# Bullseye_Volume_Board_Rev_0_0_2.net
KiCad netlist of a schematic drawn in Altium Designer
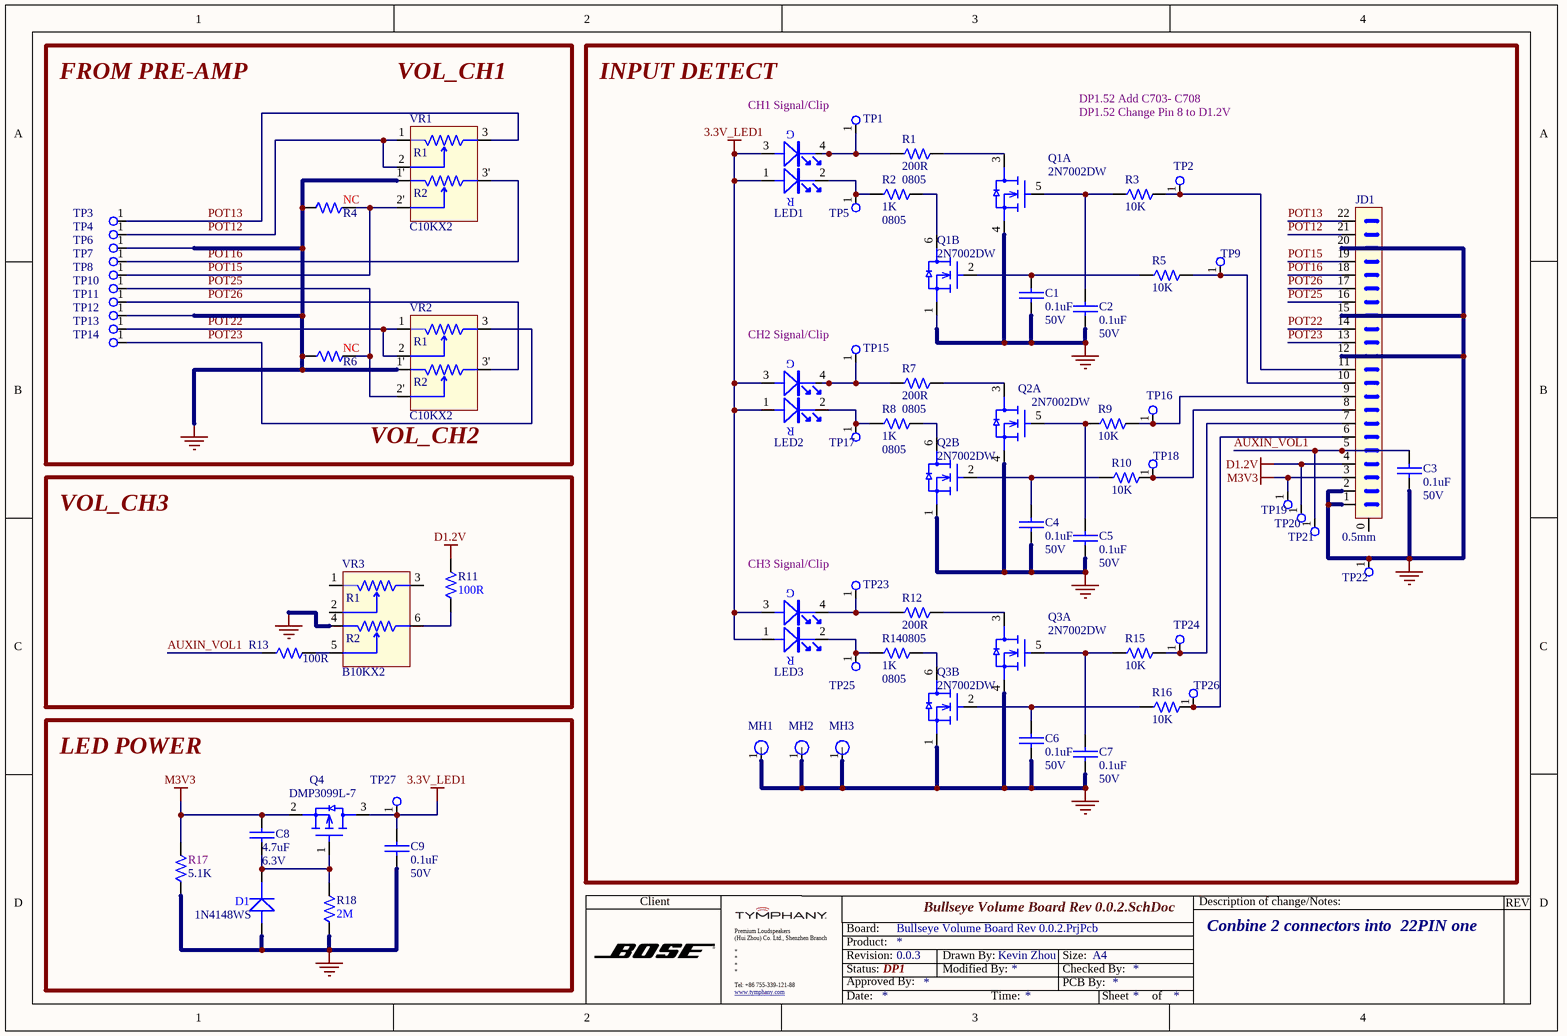
[diagram p0: Bullseye Volume Board Rev 0.0.2.SchDoc]

(export (version "E")
  (design (tool "Eeschema 10.0.6"))
  (components
    (comp (ref "C1")
      (value "0.1uF")
      (footprint "CAPC0402-RW")
      (description "CAP, CER, 0.1uF, 10%, 50V, X7R, 0402, RoHS")
      (fields
        (field (name "TOLERANCE") "10%")
        (field (name "VOLTAGE") "50V")
        (field (name "Comment") "PWL456470-1040")
        (field (name "CREATE_NAME") "TOM@Deftronics")
      )
      (libsource (lib "P-Capacitors") (part "CAP0402 0.1uF 50V 10%"))
    )
    (comp (ref "C2")
      (value "0.1uF")
      (footprint "CAPC0402-RW")
      (description "CAP, CER, 0.1uF, 10%, 50V, X7R, 0402, RoHS")
      (fields
        (field (name "TOLERANCE") "10%")
        (field (name "VOLTAGE") "50V")
        (field (name "Comment") "PWL456470-1040")
        (field (name "CREATE_NAME") "TOM@Deftronics")
      )
      (libsource (lib "P-Capacitors") (part "CAP0402 0.1uF 50V 10%"))
    )
    (comp (ref "C3")
      (value "0.1uF")
      (footprint "CAPC0402-RW")
      (description "CAP, CER, 0.1uF, 10%, 50V, X7R, 0402, RoHS")
      (fields
        (field (name "TOLERANCE") "10%")
        (field (name "VOLTAGE") "50V")
        (field (name "Comment") "PWL456470-1040")
        (field (name "CREATE_NAME") "TOM@Deftronics")
      )
      (libsource (lib "P-Capacitors") (part "CAP0402 0.1uF 50V 10%"))
    )
    (comp (ref "C4")
      (value "0.1uF")
      (footprint "CAPC0402-RW")
      (description "CAP, CER, 0.1uF, 10%, 50V, X7R, 0402, RoHS")
      (fields
        (field (name "TOLERANCE") "10%")
        (field (name "VOLTAGE") "50V")
        (field (name "Comment") "PWL456470-1040")
        (field (name "CREATE_NAME") "TOM@Deftronics")
      )
      (libsource (lib "P-Capacitors") (part "CAP0402 0.1uF 50V 10%"))
    )
    (comp (ref "C5")
      (value "0.1uF")
      (footprint "CAPC0402-RW")
      (description "CAP, CER, 0.1uF, 10%, 50V, X7R, 0402, RoHS")
      (fields
        (field (name "TOLERANCE") "10%")
        (field (name "VOLTAGE") "50V")
        (field (name "Comment") "PWL456470-1040")
        (field (name "CREATE_NAME") "TOM@Deftronics")
      )
      (libsource (lib "P-Capacitors") (part "CAP0402 0.1uF 50V 10%"))
    )
    (comp (ref "C6")
      (value "0.1uF")
      (footprint "CAPC0402-RW")
      (description "CAP, CER, 0.1uF, 10%, 50V, X7R, 0402, RoHS")
      (fields
        (field (name "TOLERANCE") "10%")
        (field (name "VOLTAGE") "50V")
        (field (name "Comment") "PWL456470-1040")
        (field (name "CREATE_NAME") "TOM@Deftronics")
      )
      (libsource (lib "P-Capacitors") (part "CAP0402 0.1uF 50V 10%"))
    )
    (comp (ref "C7")
      (value "0.1uF")
      (footprint "CAPC0402-RW")
      (description "CAP, CER, 0.1uF, 10%, 50V, X7R, 0402, RoHS")
      (fields
        (field (name "TOLERANCE") "10%")
        (field (name "VOLTAGE") "50V")
        (field (name "Comment") "PWL456470-1040")
        (field (name "CREATE_NAME") "TOM@Deftronics")
      )
      (libsource (lib "P-Capacitors") (part "CAP0402 0.1uF 50V 10%"))
    )
    (comp (ref "C8")
      (value "4.7uF")
      (footprint "CAPC0603-RW")
      (description "CHIP CAP 4.7uF 6.3V 10% 0603 TYPE X7R")
      (fields (field (name "MFG") "Walsin") (field (name "TOLERANCE") "10%") (field (name "VOLTAGE") "6.3V"))
      (libsource (lib "P-Capacitors") (part "CAP0603 4.7uF 6.3V 10% - Walsin"))
    )
    (comp (ref "C9")
      (value "0.1uF")
      (footprint "CAPC0603-RW")
      (description "GP CHIP CAP 0.1uF 50V 10% 0603 TYPE X7R")
      (fields
        (field (name "TOLERANCE") "10%")
        (field (name "VOLTAGE") "50V")
        (field (name "Comment") "PXL456470-1040")
      )
      (libsource (lib "P-Capacitors") (part "CAP0603 0.1uF 50V 10% - PXL456470-1040"))
    )
    (comp (ref "D1")
      (value "RCD114148-0020")
      (footprint "SOD-323")
      (description "DIODE SW 1N4148 VF=0.7V SOD-323")
      (fields
        (field (name "MFG") "TW SEMICONDUCTOR")
        (field (name "VOLTAGE") "100V")
        (field (name "MFG PART") "1N4148WS")
      )
      (libsource (lib "R-Semiconductors") (part "1N4148WS"))
    )
    (comp (ref "JD1")
      (value "0.5mm")
      (footprint "CONN FFC 22P PH=0.5mm SMT RA 0.5S-1X-22PWT-5.4R")
      (description "22P P=0.5MM 180 K")
      (fields
        (field (name "MFG") "金佳")
        (field (name "MFG PART") "0.5S-1X-22PWT-5.4R")
        (field (name "CREATE_NAME") "Nathan")
      )
      (libsource (lib "C-Connector") (part "CONN FFC 22P PH=0.5mm SMT RA 0.5S-1X-22PWT-5.4R"))
    )
    (comp (ref "LED1")
      (value "KCD250001-0010")
      (footprint "SMTLED2.0*1.25-RGB")
      (description "SMD LED 2.0x1.25mm MS-PTB2012CURSGAC  RED/GREEN")
      (fields
        (field (name "MFG PART") "MS-PTB2012CURSGAC  RED/GREEN")
        (field (name "MFG") "MASON")
        (field (name "CREATE_NAME") "TOM@Deftronics")
      )
      (libsource (lib "K-LED-FUSE") (part "MS-PTB2012CURSGAC"))
    )
    (comp (ref "LED2")
      (value "KCD250001-0010")
      (footprint "SMTLED2.0*1.25-RGB")
      (description "SMD LED 2.0x1.25mm MS-PTB2012CURSGAC  RED/GREEN")
      (fields
        (field (name "MFG PART") "MS-PTB2012CURSGAC  RED/GREEN")
        (field (name "MFG") "MASON")
        (field (name "CREATE_NAME") "TOM@Deftronics")
      )
      (libsource (lib "K-LED-FUSE") (part "MS-PTB2012CURSGAC"))
    )
    (comp (ref "LED3")
      (value "KCD250001-0010")
      (footprint "SMTLED2.0*1.25-RGB")
      (description "SMD LED 2.0x1.25mm MS-PTB2012CURSGAC  RED/GREEN")
      (fields
        (field (name "MFG PART") "MS-PTB2012CURSGAC  RED/GREEN")
        (field (name "MFG") "MASON")
        (field (name "CREATE_NAME") "TOM@Deftronics")
      )
      (libsource (lib "K-LED-FUSE") (part "MS-PTB2012CURSGAC"))
    )
    (comp (ref "MH1")
      (value "MHOLE 3MM")
      (footprint "MHOLE 3.5MM W/Vias")
      (description "MOUNTING HOLE FOR 3MM SCREW")
      (libsource (lib "Temporary") (part "MHOLE 3MM"))
    )
    (comp (ref "MH2")
      (value "MHOLE 3MM")
      (footprint "MHOLE 3.5MM W/Vias")
      (description "MOUNTING HOLE FOR 3MM SCREW")
      (libsource (lib "Temporary") (part "MHOLE 3MM"))
    )
    (comp (ref "MH3")
      (value "MHOLE 3MM")
      (footprint "MHOLE 3.5MM W/Vias")
      (description "MOUNTING HOLE FOR 3MM SCREW")
      (libsource (lib "Temporary") (part "MHOLE 3MM"))
    )
    (comp (ref "Q1")
      (value "RCM027002-1001")
      (footprint "SOT-363")
      (description "SMD MOSFET N-CH SOT-363 2N7002DW      Fairchild")
      (fields
        (field (name "MFG") "Fairchild")
        (field (name "MFG_PART") "2N7002DW")
        (field (name "CREATE_NAME") "Evan@Deftronics")
      )
      (libsource (lib "R-Semiconductors") (part "2N7002DW"))
    )
    (comp (ref "Q2")
      (value "RCM027002-1001")
      (footprint "SOT-363")
      (description "SMD MOSFET N-CH SOT-363 2N7002DW      Fairchild")
      (fields
        (field (name "MFG") "Fairchild")
        (field (name "MFG_PART") "2N7002DW")
        (field (name "CREATE_NAME") "Evan@Deftronics")
      )
      (libsource (lib "R-Semiconductors") (part "2N7002DW"))
    )
    (comp (ref "Q3")
      (value "RCM027002-1001")
      (footprint "SOT-363")
      (description "SMD MOSFET N-CH SOT-363 2N7002DW      Fairchild")
      (fields
        (field (name "MFG") "Fairchild")
        (field (name "MFG_PART") "2N7002DW")
        (field (name "CREATE_NAME") "Evan@Deftronics")
      )
      (libsource (lib "R-Semiconductors") (part "2N7002DW"))
    )
    (comp (ref "Q4")
      (value "T585002550438")
      (footprint "SOT23-132-RW")
      (description "PMOS 20V DMP3099L-7 SOT23 DIODES K")
      (fields
        (field (name "MFG") "DIODES  (ZETEX)")
        (field (name "MFG PART") "DMP3099L-7")
        (field (name "CREATE_NAME") "Nathan")
      )
      (libsource (lib "R-Semiconductors") (part "DMP3099L-7"))
    )
    (comp (ref "R1")
      (value "200R")
      (footprint "0805-RW")
      (description "GP CHIP RES. 200 OHM 1/8W 1% 0805")
      (fields (field (name "PACKAGE") "0805") (field (name "Comment") "QCF081020-2000"))
      (libsource (lib "Q-Resistors") (part "RES0805 1/8W 1% 200 OHM"))
    )
    (comp (ref "R2")
      (value "1K")
      (footprint "0805-RW")
      (description "GP CHIP RES. 1K OHM 1/8W 1% 0805")
      (fields (field (name "PACKAGE") "0805") (field (name "Comment") "QCF081020-1001"))
      (libsource (lib "Q-Resistors") (part "RES0805 1/8W 1% 1K OHM"))
    )
    (comp (ref "R3")
      (value "10K")
      (footprint "0402-RW")
      (description "CHIP RES 10K OHM 1/16W 1% 0402")
      (fields (field (name "MFG") "WALSIN") (field (name "Comment") "QCF161240-1002"))
      (libsource (lib "Q-Resistors") (part "RES0402 1/16W 1% 10K OHM"))
    )
    (comp (ref "R4")
      (value "NC")
      (footprint "0603-RW")
      (fields (field (name "Comment") "RES0603 NC") (field (name "CREATE_NAME") "Tom"))
      (libsource (lib "Temporary") (part "RES0603 NC"))
    )
    (comp (ref "R5")
      (value "10K")
      (footprint "0402-RW")
      (description "CHIP RES 10K OHM 1/16W 1% 0402")
      (fields (field (name "MFG") "WALSIN") (field (name "Comment") "QCF161240-1002"))
      (libsource (lib "Q-Resistors") (part "RES0402 1/16W 1% 10K OHM"))
    )
    (comp (ref "R6")
      (value "NC")
      (footprint "0603-RW")
      (fields (field (name "Comment") "RES0603 NC") (field (name "CREATE_NAME") "Tom"))
      (libsource (lib "Temporary") (part "RES0603 NC"))
    )
    (comp (ref "R7")
      (value "200R")
      (footprint "0805-RW")
      (description "GP CHIP RES. 200 OHM 1/8W 1% 0805")
      (fields (field (name "PACKAGE") "0805") (field (name "Comment") "QCF081020-2000"))
      (libsource (lib "Q-Resistors") (part "RES0805 1/8W 1% 200 OHM"))
    )
    (comp (ref "R8")
      (value "1K")
      (footprint "0805-RW")
      (description "GP CHIP RES. 1K OHM 1/8W 1% 0805")
      (fields (field (name "PACKAGE") "0805") (field (name "Comment") "QCF081020-1001"))
      (libsource (lib "Q-Resistors") (part "RES0805 1/8W 1% 1K OHM"))
    )
    (comp (ref "R9")
      (value "10K")
      (footprint "0402-RW")
      (description "CHIP RES 10K OHM 1/16W 1% 0402")
      (fields (field (name "MFG") "WALSIN") (field (name "Comment") "QCF161240-1002"))
      (libsource (lib "Q-Resistors") (part "RES0402 1/16W 1% 10K OHM"))
    )
    (comp (ref "R10")
      (value "10K")
      (footprint "0402-RW")
      (description "CHIP RES 10K OHM 1/16W 1% 0402")
      (fields (field (name "MFG") "WALSIN") (field (name "Comment") "QCF161240-1002"))
      (libsource (lib "Q-Resistors") (part "RES0402 1/16W 1% 10K OHM"))
    )
    (comp (ref "R11")
      (value "100R")
      (footprint "0402-RW")
      (description "CHIP RES 100 OHM 1/16W 1% 0402")
      (fields (field (name "MFG") "WALSIN") (field (name "Comment") "QCF161240-1000"))
      (libsource (lib "Q-Resistors") (part "RES0402 1/16W 1% 100 OHM"))
    )
    (comp (ref "R12")
      (value "200R")
      (footprint "0805-RW")
      (description "GP CHIP RES. 200 OHM 1/8W 1% 0805")
      (fields (field (name "PACKAGE") "0805") (field (name "Comment") "QCF081020-2000"))
      (libsource (lib "Q-Resistors") (part "RES0805 1/8W 1% 200 OHM"))
    )
    (comp (ref "R13")
      (value "100R")
      (footprint "0402-RW")
      (description "CHIP RES 100 OHM 1/16W 1% 0402")
      (fields (field (name "POWER") "1/16W") (field (name "MFG") "WALSIN"))
      (libsource (lib "Q-Resistors") (part "RES0402 1/16W 1% 100 OHM"))
    )
    (comp (ref "R14")
      (value "1K")
      (footprint "0805-RW")
      (description "GP CHIP RES. 1K OHM 1/8W 1% 0805")
      (fields (field (name "PACKAGE") "0805") (field (name "Comment") "QCF081020-1001"))
      (libsource (lib "Q-Resistors") (part "RES0805 1/8W 1% 1K OHM"))
    )
    (comp (ref "R15")
      (value "10K")
      (footprint "0402-RW")
      (description "CHIP RES 10K OHM 1/16W 1% 0402")
      (fields (field (name "MFG") "WALSIN") (field (name "Comment") "QCF161240-1002"))
      (libsource (lib "Q-Resistors") (part "RES0402 1/16W 1% 10K OHM"))
    )
    (comp (ref "R16")
      (value "10K")
      (footprint "0402-RW")
      (description "CHIP RES 10K OHM 1/16W 1% 0402")
      (fields (field (name "MFG") "WALSIN") (field (name "Comment") "QCF161240-1002"))
      (libsource (lib "Q-Resistors") (part "RES0402 1/16W 1% 10K OHM"))
    )
    (comp (ref "R17")
      (value "5.1K")
      (footprint "0603-RW")
      (description "GP CHIP RES. 5.1K OHM 1/10W 1% 0603")
      (fields (field (name "Comment") "QCF011030-5101"))
      (libsource (lib "Q-Resistors") (part "RES0603 1/10W 1% 5.1K OHM"))
    )
    (comp (ref "R18")
      (value "2M")
      (footprint "0402-RW")
      (description "CHIP 2M OHM    100PPM +-1% 0402 WALS L")
      (fields
        (field (name "MFG") "WALSIN (華新)")
        (field (name "POWER") "1/16W")
        (field (name "CREATE_NAME") "Nathan")
      )
      (libsource (lib "Q-Resistors") (part "RES0402 1/16W 1% 2M OMH_WALSIN"))
    )
    (comp (ref "TP1")
      (value "CH1_GN")
      (footprint "TP_1.2mm")
      (description "TP")
      (libsource (lib "Temporary") (part "TP"))
    )
    (comp (ref "TP2")
      (value "CH1_SIG")
      (footprint "TP_1.2mm")
      (description "TP")
      (libsource (lib "Temporary") (part "TP"))
    )
    (comp (ref "TP3")
      (value "CH1_GN")
      (footprint "TP_1.2mm")
      (description "TP")
      (libsource (lib "Temporary") (part "TP"))
    )
    (comp (ref "TP4")
      (value "CH1_GN")
      (footprint "TP_1.2mm")
      (description "TP")
      (libsource (lib "Temporary") (part "TP"))
    )
    (comp (ref "TP5")
      (value "CH1_RED")
      (footprint "TP_1.2mm")
      (description "TP")
      (libsource (lib "Temporary") (part "TP"))
    )
    (comp (ref "TP6")
      (value "CH1_GN")
      (footprint "TP_1.2mm")
      (description "TP")
      (libsource (lib "Temporary") (part "TP"))
    )
    (comp (ref "TP7")
      (value "CH1_GN")
      (footprint "TP_1.2mm")
      (description "TP")
      (libsource (lib "Temporary") (part "TP"))
    )
    (comp (ref "TP8")
      (value "CH1_GN")
      (footprint "TP_1.2mm")
      (description "TP")
      (libsource (lib "Temporary") (part "TP"))
    )
    (comp (ref "TP9")
      (value "CH1_LIM")
      (footprint "TP_1.2mm")
      (description "TP")
      (libsource (lib "Temporary") (part "TP"))
    )
    (comp (ref "TP10")
      (value "CH1_GN")
      (footprint "TP_1.2mm")
      (description "TP")
      (libsource (lib "Temporary") (part "TP"))
    )
    (comp (ref "TP11")
      (value "CH1_GN")
      (footprint "TP_1.2mm")
      (description "TP")
      (libsource (lib "Temporary") (part "TP"))
    )
    (comp (ref "TP12")
      (value "CH1_GN")
      (footprint "TP_1.2mm")
      (description "TP")
      (libsource (lib "Temporary") (part "TP"))
    )
    (comp (ref "TP13")
      (value "CH1_GN")
      (footprint "TP_1.2mm")
      (description "TP")
      (libsource (lib "Temporary") (part "TP"))
    )
    (comp (ref "TP14")
      (value "CH1_GN")
      (footprint "TP_1.2mm")
      (description "TP")
      (libsource (lib "Temporary") (part "TP"))
    )
    (comp (ref "TP15")
      (value "CH1_GN")
      (footprint "TP_1.2mm")
      (description "TP")
      (libsource (lib "Temporary") (part "TP"))
    )
    (comp (ref "TP16")
      (value "CH1_SIG")
      (footprint "TP_1.2mm")
      (description "TP")
      (libsource (lib "Temporary") (part "TP"))
    )
    (comp (ref "TP17")
      (value "CH1_RED")
      (footprint "TP_1.2mm")
      (description "TP")
      (libsource (lib "Temporary") (part "TP"))
    )
    (comp (ref "TP18")
      (value "CH1_LIM")
      (footprint "TP_1.2mm")
      (description "TP")
      (libsource (lib "Temporary") (part "TP"))
    )
    (comp (ref "TP19")
      (value "CH1_LIM")
      (footprint "TP_1.2mm")
      (description "TP")
      (libsource (lib "Temporary") (part "TP"))
    )
    (comp (ref "TP20")
      (value "CH1_LIM")
      (footprint "TP_1.2mm")
      (description "TP")
      (libsource (lib "Temporary") (part "TP"))
    )
    (comp (ref "TP21")
      (value "CH1_LIM")
      (footprint "TP_1.2mm")
      (description "TP")
      (libsource (lib "Temporary") (part "TP"))
    )
    (comp (ref "TP22")
      (value "CH1_LIM")
      (footprint "TP_1.2mm")
      (description "TP")
      (libsource (lib "Temporary") (part "TP"))
    )
    (comp (ref "TP23")
      (value "CH1_GN")
      (footprint "TP_1.2mm")
      (description "TP")
      (libsource (lib "Temporary") (part "TP"))
    )
    (comp (ref "TP24")
      (value "CH1_SIG")
      (footprint "TP_1.2mm")
      (description "TP")
      (libsource (lib "Temporary") (part "TP"))
    )
    (comp (ref "TP25")
      (value "CH1_RED")
      (footprint "TP_1.2mm")
      (description "TP")
      (libsource (lib "Temporary") (part "TP"))
    )
    (comp (ref "TP26")
      (value "CH1_LIM")
      (footprint "TP_1.2mm")
      (description "TP")
      (libsource (lib "Temporary") (part "TP"))
    )
    (comp (ref "TP27")
      (value "CH2_SIG")
      (footprint "TP_1.2mm")
      (description "TP")
      (libsource (lib "Temporary") (part "TP"))
    )
    (comp (ref "VR1")
      (value "C10KX2")
      (footprint "R11122G-FA20B7-5C103-167")
      (description "VR CA 10K C L=20MM R11122G-F K")
      (fields
        (field (name "MFG") "IDEAL")
        (field (name "MFG PART") "R11122G-FA20B7-5C103-167")
        (field (name "CREATE_NAME") "Nathan")
      )
      (libsource (lib "M-Controls") (part "R11122G-FA20B7-5C103-167"))
    )
    (comp (ref "VR2")
      (value "C10KX2")
      (footprint "R11122G-FA20B7-5C103-167")
      (description "VR CA 10K C L=20MM R11122G-F K")
      (fields
        (field (name "MFG") "IDEAL")
        (field (name "MFG PART") "R11122G-FA20B7-5C103-167")
        (field (name "CREATE_NAME") "Nathan")
      )
      (libsource (lib "M-Controls") (part "R11122G-FA20B7-5C103-167"))
    )
    (comp (ref "VR3")
      (value "B10KX2")
      (footprint "RV112BCF-40-20A-B10K-0C")
      (description "VR CA 10K B 15.4X13MM RV112BCF- K")
      (fields
        (field (name "MFG") "ALPHA    (東莞艾華電子)")
        (field (name "MFG PART") "RV112BCF-40-20A-B10K-0C")
        (field (name "CREATE_NAME") "Nathan")
      )
      (libsource (lib "M-Controls") (part "RV112BCF-40-20A-B10K-0C"))
    )
  )
  (nets
    (net (code "1") (name "/AUXIN_VOL1") (class "Default")
      (node (ref "C3") (pin "1") (pinfunction "1_1") (pintype "passive"))
      (node (ref "JD1") (pin "5") (pinfunction "5_5") (pintype "passive"))
      (node (ref "R13") (pin "1") (pinfunction "1_1") (pintype "passive"))
      (node (ref "TP21") (pin "1") (pinfunction "1_1") (pintype "passive"))
    )
    (net (code "2") (name "/POT12") (class "Default")
      (node (ref "JD1") (pin "21") (pinfunction "21_21") (pintype "passive"))
      (node (ref "TP4") (pin "1") (pinfunction "1_1") (pintype "passive"))
      (node (ref "VR1") (pin "1") (pinfunction "1_1") (pintype "passive"))
      (node (ref "VR1") (pin "2") (pinfunction "2_2") (pintype "passive"))
    )
    (net (code "3") (name "/POT13") (class "Default")
      (node (ref "JD1") (pin "22") (pinfunction "22_22") (pintype "passive"))
      (node (ref "TP3") (pin "1") (pinfunction "1_1") (pintype "passive"))
      (node (ref "VR1") (pin "3") (pinfunction "3_3") (pintype "passive"))
    )
    (net (code "4") (name "/POT15") (class "Default")
      (node (ref "JD1") (pin "19") (pinfunction "19_19") (pintype "passive"))
      (node (ref "R4") (pin "1") (pinfunction "1_1") (pintype "passive"))
      (node (ref "TP8") (pin "1") (pinfunction "1_1") (pintype "passive"))
      (node (ref "VR1") (pin "2'") (pinfunction "2'_2'") (pintype "passive"))
    )
    (net (code "5") (name "/POT16") (class "Default")
      (node (ref "JD1") (pin "18") (pinfunction "18_18") (pintype "passive"))
      (node (ref "TP7") (pin "1") (pinfunction "1_1") (pintype "passive"))
      (node (ref "VR1") (pin "3'") (pinfunction "3'_3'") (pintype "passive"))
    )
    (net (code "6") (name "/POT22") (class "Default")
      (node (ref "JD1") (pin "14") (pinfunction "14_14") (pintype "passive"))
      (node (ref "TP13") (pin "1") (pinfunction "1_1") (pintype "passive"))
      (node (ref "VR2") (pin "1") (pinfunction "1_1") (pintype "passive"))
      (node (ref "VR2") (pin "2") (pinfunction "2_2") (pintype "passive"))
    )
    (net (code "7") (name "/POT23") (class "Default")
      (node (ref "JD1") (pin "13") (pinfunction "13_13") (pintype "passive"))
      (node (ref "TP14") (pin "1") (pinfunction "1_1") (pintype "passive"))
      (node (ref "VR2") (pin "3") (pinfunction "3_3") (pintype "passive"))
    )
    (net (code "8") (name "/POT25") (class "Default")
      (node (ref "JD1") (pin "16") (pinfunction "16_16") (pintype "passive"))
      (node (ref "R6") (pin "2") (pinfunction "2_2") (pintype "passive"))
      (node (ref "TP10") (pin "1") (pinfunction "1_1") (pintype "passive"))
      (node (ref "VR2") (pin "2'") (pinfunction "2'_2'") (pintype "passive"))
    )
    (net (code "9") (name "/POT26") (class "Default")
      (node (ref "JD1") (pin "17") (pinfunction "17_17") (pintype "passive"))
      (node (ref "TP11") (pin "1") (pinfunction "1_1") (pintype "passive"))
      (node (ref "VR2") (pin "3'") (pinfunction "3'_3'") (pintype "passive"))
    )
    (net (code "10") (name "3.3V_LED1") (class "Default")
      (node (ref "C9") (pin "2") (pinfunction "2_2") (pintype "passive"))
      (node (ref "LED1") (pin "1") (pinfunction "1_1") (pintype "passive"))
      (node (ref "LED1") (pin "3") (pinfunction "3_3") (pintype "passive"))
      (node (ref "LED2") (pin "1") (pinfunction "1_1") (pintype "passive"))
      (node (ref "LED2") (pin "3") (pinfunction "3_3") (pintype "passive"))
      (node (ref "LED3") (pin "1") (pinfunction "1_1") (pintype "passive"))
      (node (ref "LED3") (pin "3") (pinfunction "3_3") (pintype "passive"))
      (node (ref "Q4") (pin "3") (pinfunction "D_3") (pintype "passive"))
      (node (ref "TP27") (pin "1") (pinfunction "1_1") (pintype "passive"))
    )
    (net (code "11") (name "D1.2V") (class "Default")
      (node (ref "JD1") (pin "4") (pinfunction "4_4") (pintype "passive"))
      (node (ref "R11") (pin "2") (pinfunction "2_2") (pintype "passive"))
      (node (ref "TP20") (pin "1") (pinfunction "1_1") (pintype "passive"))
    )
    (net (code "12") (name "GND") (class "Default")
      (node (ref "C1") (pin "2") (pinfunction "2_2") (pintype "passive"))
      (node (ref "C2") (pin "2") (pinfunction "2_2") (pintype "passive"))
      (node (ref "C3") (pin "2") (pinfunction "2_2") (pintype "passive"))
      (node (ref "C4") (pin "2") (pinfunction "2_2") (pintype "passive"))
      (node (ref "C5") (pin "2") (pinfunction "2_2") (pintype "passive"))
      (node (ref "C6") (pin "2") (pinfunction "2_2") (pintype "passive"))
      (node (ref "C7") (pin "2") (pinfunction "2_2") (pintype "passive"))
      (node (ref "C9") (pin "1") (pinfunction "1_1") (pintype "passive"))
      (node (ref "D1") (pin "1") (pinfunction "A_1") (pintype "passive"))
      (node (ref "JD1") (pin "1") (pinfunction "1_1") (pintype "passive"))
      (node (ref "JD1") (pin "12") (pinfunction "12_12") (pintype "passive"))
      (node (ref "JD1") (pin "15") (pinfunction "15_15") (pintype "passive"))
      (node (ref "JD1") (pin "2") (pinfunction "2_2") (pintype "passive"))
      (node (ref "JD1") (pin "20") (pinfunction "20_20") (pintype "passive"))
      (node (ref "MH1") (pin "1") (pinfunction "1_1") (pintype "passive"))
      (node (ref "MH2") (pin "1") (pinfunction "1_1") (pintype "passive"))
      (node (ref "MH3") (pin "1") (pinfunction "1_1") (pintype "passive"))
      (node (ref "Q1") (pin "1") (pinfunction "S_1") (pintype "passive"))
      (node (ref "Q1") (pin "4") (pinfunction "S_4") (pintype "passive"))
      (node (ref "Q2") (pin "1") (pinfunction "S_1") (pintype "passive"))
      (node (ref "Q2") (pin "4") (pinfunction "S_4") (pintype "passive"))
      (node (ref "Q3") (pin "1") (pinfunction "S_1") (pintype "passive"))
      (node (ref "Q3") (pin "4") (pinfunction "S_4") (pintype "passive"))
      (node (ref "R17") (pin "1") (pinfunction "1_1") (pintype "passive"))
      (node (ref "R18") (pin "1") (pinfunction "1_1") (pintype "passive"))
      (node (ref "R4") (pin "2") (pinfunction "2_2") (pintype "passive"))
      (node (ref "R6") (pin "1") (pinfunction "1_1") (pintype "passive"))
      (node (ref "TP12") (pin "1") (pinfunction "1_1") (pintype "passive"))
      (node (ref "TP22") (pin "1") (pinfunction "1_1") (pintype "passive"))
      (node (ref "TP6") (pin "1") (pinfunction "1_1") (pintype "passive"))
      (node (ref "VR1") (pin "1'") (pinfunction "1'_1'") (pintype "passive"))
      (node (ref "VR2") (pin "1'") (pinfunction "1'_1'") (pintype "passive"))
      (node (ref "VR3") (pin "4") (pinfunction "4_4") (pintype "passive"))
    )
    (net (code "13") (name "M3V3") (class "Default")
      (node (ref "C8") (pin "1") (pinfunction "1_1") (pintype "passive"))
      (node (ref "JD1") (pin "3") (pinfunction "3_3") (pintype "passive"))
      (node (ref "Q4") (pin "2") (pinfunction "S_2") (pintype "passive"))
      (node (ref "R17") (pin "2") (pinfunction "2_2") (pintype "passive"))
      (node (ref "TP19") (pin "1") (pinfunction "1_1") (pintype "passive"))
    )
    (net (code "14") (name "Net-(D1-K)") (class "Default")
      (node (ref "C8") (pin "2") (pinfunction "2_2") (pintype "passive"))
      (node (ref "D1") (pin "2") (pinfunction "K_2") (pintype "passive"))
      (node (ref "Q4") (pin "1") (pinfunction "G_1") (pintype "passive"))
      (node (ref "R18") (pin "2") (pinfunction "2_2") (pintype "passive"))
    )
    (net (code "15") (name "Net-(JD1-Pad6)") (class "Default")
      (node (ref "JD1") (pin "6") (pinfunction "6_6") (pintype "passive"))
      (node (ref "R16") (pin "2") (pinfunction "2_2") (pintype "passive"))
      (node (ref "TP26") (pin "1") (pinfunction "1_1") (pintype "passive"))
    )
    (net (code "16") (name "Net-(JD1-Pad7)") (class "Default")
      (node (ref "JD1") (pin "7") (pinfunction "7_7") (pintype "passive"))
      (node (ref "R15") (pin "2") (pinfunction "2_2") (pintype "passive"))
      (node (ref "TP24") (pin "1") (pinfunction "1_1") (pintype "passive"))
    )
    (net (code "17") (name "Net-(JD1-Pad8)") (class "Default")
      (node (ref "JD1") (pin "8") (pinfunction "8_8") (pintype "passive"))
      (node (ref "R10") (pin "2") (pinfunction "2_2") (pintype "passive"))
      (node (ref "TP18") (pin "1") (pinfunction "1_1") (pintype "passive"))
    )
    (net (code "18") (name "Net-(JD1-Pad9)") (class "Default")
      (node (ref "JD1") (pin "9") (pinfunction "9_9") (pintype "passive"))
      (node (ref "R9") (pin "2") (pinfunction "2_2") (pintype "passive"))
      (node (ref "TP16") (pin "1") (pinfunction "1_1") (pintype "passive"))
    )
    (net (code "19") (name "Net-(JD1-Pad10)") (class "Default")
      (node (ref "JD1") (pin "10") (pinfunction "10_10") (pintype "passive"))
      (node (ref "R5") (pin "2") (pinfunction "2_2") (pintype "passive"))
      (node (ref "TP9") (pin "1") (pinfunction "1_1") (pintype "passive"))
    )
    (net (code "20") (name "Net-(JD1-Pad11)") (class "Default")
      (node (ref "JD1") (pin "11") (pinfunction "11_11") (pintype "passive"))
      (node (ref "R3") (pin "2") (pinfunction "2_2") (pintype "passive"))
      (node (ref "TP2") (pin "1") (pinfunction "1_1") (pintype "passive"))
    )
    (net (code "21") (name "Net-(LED1-Pad2)") (class "Default")
      (node (ref "LED1") (pin "2") (pinfunction "2_2") (pintype "passive"))
      (node (ref "R2") (pin "1") (pinfunction "1_1") (pintype "passive"))
      (node (ref "TP5") (pin "1") (pinfunction "1_1") (pintype "passive"))
    )
    (net (code "22") (name "Net-(LED1-Pad4)") (class "Default")
      (node (ref "LED1") (pin "4") (pinfunction "4_4") (pintype "passive"))
      (node (ref "R1") (pin "1") (pinfunction "1_1") (pintype "passive"))
      (node (ref "TP1") (pin "1") (pinfunction "1_1") (pintype "passive"))
    )
    (net (code "23") (name "Net-(LED2-Pad2)") (class "Default")
      (node (ref "LED2") (pin "2") (pinfunction "2_2") (pintype "passive"))
      (node (ref "R8") (pin "1") (pinfunction "1_1") (pintype "passive"))
      (node (ref "TP17") (pin "1") (pinfunction "1_1") (pintype "passive"))
    )
    (net (code "24") (name "Net-(LED2-Pad4)") (class "Default")
      (node (ref "LED2") (pin "4") (pinfunction "4_4") (pintype "passive"))
      (node (ref "R7") (pin "1") (pinfunction "1_1") (pintype "passive"))
      (node (ref "TP15") (pin "1") (pinfunction "1_1") (pintype "passive"))
    )
    (net (code "25") (name "Net-(LED3-Pad2)") (class "Default")
      (node (ref "LED3") (pin "2") (pinfunction "2_2") (pintype "passive"))
      (node (ref "R14") (pin "1") (pinfunction "1_1") (pintype "passive"))
      (node (ref "TP25") (pin "1") (pinfunction "1_1") (pintype "passive"))
    )
    (net (code "26") (name "Net-(LED3-Pad4)") (class "Default")
      (node (ref "LED3") (pin "4") (pinfunction "4_4") (pintype "passive"))
      (node (ref "R12") (pin "1") (pinfunction "1_1") (pintype "passive"))
      (node (ref "TP23") (pin "1") (pinfunction "1_1") (pintype "passive"))
    )
    (net (code "27") (name "Net-(Q1A-D)") (class "Default")
      (node (ref "Q1") (pin "3") (pinfunction "D_3") (pintype "passive"))
      (node (ref "R1") (pin "2") (pinfunction "2_2") (pintype "passive"))
    )
    (net (code "28") (name "Net-(Q1A-G)") (class "Default")
      (node (ref "C2") (pin "1") (pinfunction "1_1") (pintype "passive"))
      (node (ref "Q1") (pin "5") (pinfunction "G_5") (pintype "passive"))
      (node (ref "R3") (pin "1") (pinfunction "1_1") (pintype "passive"))
    )
    (net (code "29") (name "Net-(Q1B-D)") (class "Default")
      (node (ref "Q1") (pin "6") (pinfunction "D_6") (pintype "passive"))
      (node (ref "R2") (pin "2") (pinfunction "2_2") (pintype "passive"))
    )
    (net (code "30") (name "Net-(Q1B-G)") (class "Default")
      (node (ref "C1") (pin "1") (pinfunction "1_1") (pintype "passive"))
      (node (ref "Q1") (pin "2") (pinfunction "G_2") (pintype "passive"))
      (node (ref "R5") (pin "1") (pinfunction "1_1") (pintype "passive"))
    )
    (net (code "31") (name "Net-(Q2A-D)") (class "Default")
      (node (ref "Q2") (pin "3") (pinfunction "D_3") (pintype "passive"))
      (node (ref "R7") (pin "2") (pinfunction "2_2") (pintype "passive"))
    )
    (net (code "32") (name "Net-(Q2A-G)") (class "Default")
      (node (ref "C5") (pin "1") (pinfunction "1_1") (pintype "passive"))
      (node (ref "Q2") (pin "5") (pinfunction "G_5") (pintype "passive"))
      (node (ref "R9") (pin "1") (pinfunction "1_1") (pintype "passive"))
    )
    (net (code "33") (name "Net-(Q2B-D)") (class "Default")
      (node (ref "Q2") (pin "6") (pinfunction "D_6") (pintype "passive"))
      (node (ref "R8") (pin "2") (pinfunction "2_2") (pintype "passive"))
    )
    (net (code "34") (name "Net-(Q2B-G)") (class "Default")
      (node (ref "C4") (pin "1") (pinfunction "1_1") (pintype "passive"))
      (node (ref "Q2") (pin "2") (pinfunction "G_2") (pintype "passive"))
      (node (ref "R10") (pin "1") (pinfunction "1_1") (pintype "passive"))
    )
    (net (code "35") (name "Net-(Q3A-D)") (class "Default")
      (node (ref "Q3") (pin "3") (pinfunction "D_3") (pintype "passive"))
      (node (ref "R12") (pin "2") (pinfunction "2_2") (pintype "passive"))
    )
    (net (code "36") (name "Net-(Q3A-G)") (class "Default")
      (node (ref "C7") (pin "1") (pinfunction "1_1") (pintype "passive"))
      (node (ref "Q3") (pin "5") (pinfunction "G_5") (pintype "passive"))
      (node (ref "R15") (pin "1") (pinfunction "1_1") (pintype "passive"))
    )
    (net (code "37") (name "Net-(Q3B-D)") (class "Default")
      (node (ref "Q3") (pin "6") (pinfunction "D_6") (pintype "passive"))
      (node (ref "R14") (pin "2") (pinfunction "2_2") (pintype "passive"))
    )
    (net (code "38") (name "Net-(Q3B-G)") (class "Default")
      (node (ref "C6") (pin "1") (pinfunction "1_1") (pintype "passive"))
      (node (ref "Q3") (pin "2") (pinfunction "G_2") (pintype "passive"))
      (node (ref "R16") (pin "1") (pinfunction "1_1") (pintype "passive"))
    )
    (net (code "39") (name "Net-(R11-Pad1)") (class "Default")
      (node (ref "R11") (pin "1") (pinfunction "1_1") (pintype "passive"))
      (node (ref "VR3") (pin "6") (pinfunction "6_6") (pintype "passive"))
    )
    (net (code "40") (name "Net-(R13-Pad2)") (class "Default")
      (node (ref "R13") (pin "2") (pinfunction "2_2") (pintype "passive"))
      (node (ref "VR3") (pin "5") (pinfunction "5_5") (pintype "passive"))
    )
    (net (code "41") (name "unconnected-(JD1-Pad0)") (class "Default")
      (node (ref "JD1") (pin "0") (pinfunction "0_0") (pintype "passive"))
    )
    (net (code "42") (name "unconnected-(VR3-Pad1)") (class "Default")
      (node (ref "VR3") (pin "1") (pinfunction "1_1") (pintype "passive"))
    )
    (net (code "43") (name "unconnected-(VR3-Pad2)") (class "Default")
      (node (ref "VR3") (pin "2") (pinfunction "2_2") (pintype "passive"))
    )
    (net (code "44") (name "unconnected-(VR3-Pad3)") (class "Default")
      (node (ref "VR3") (pin "3") (pinfunction "3_3") (pintype "passive"))
    )
  )
)
